# lite_version.net
KiCad netlist of a schematic drawn in EAGLE
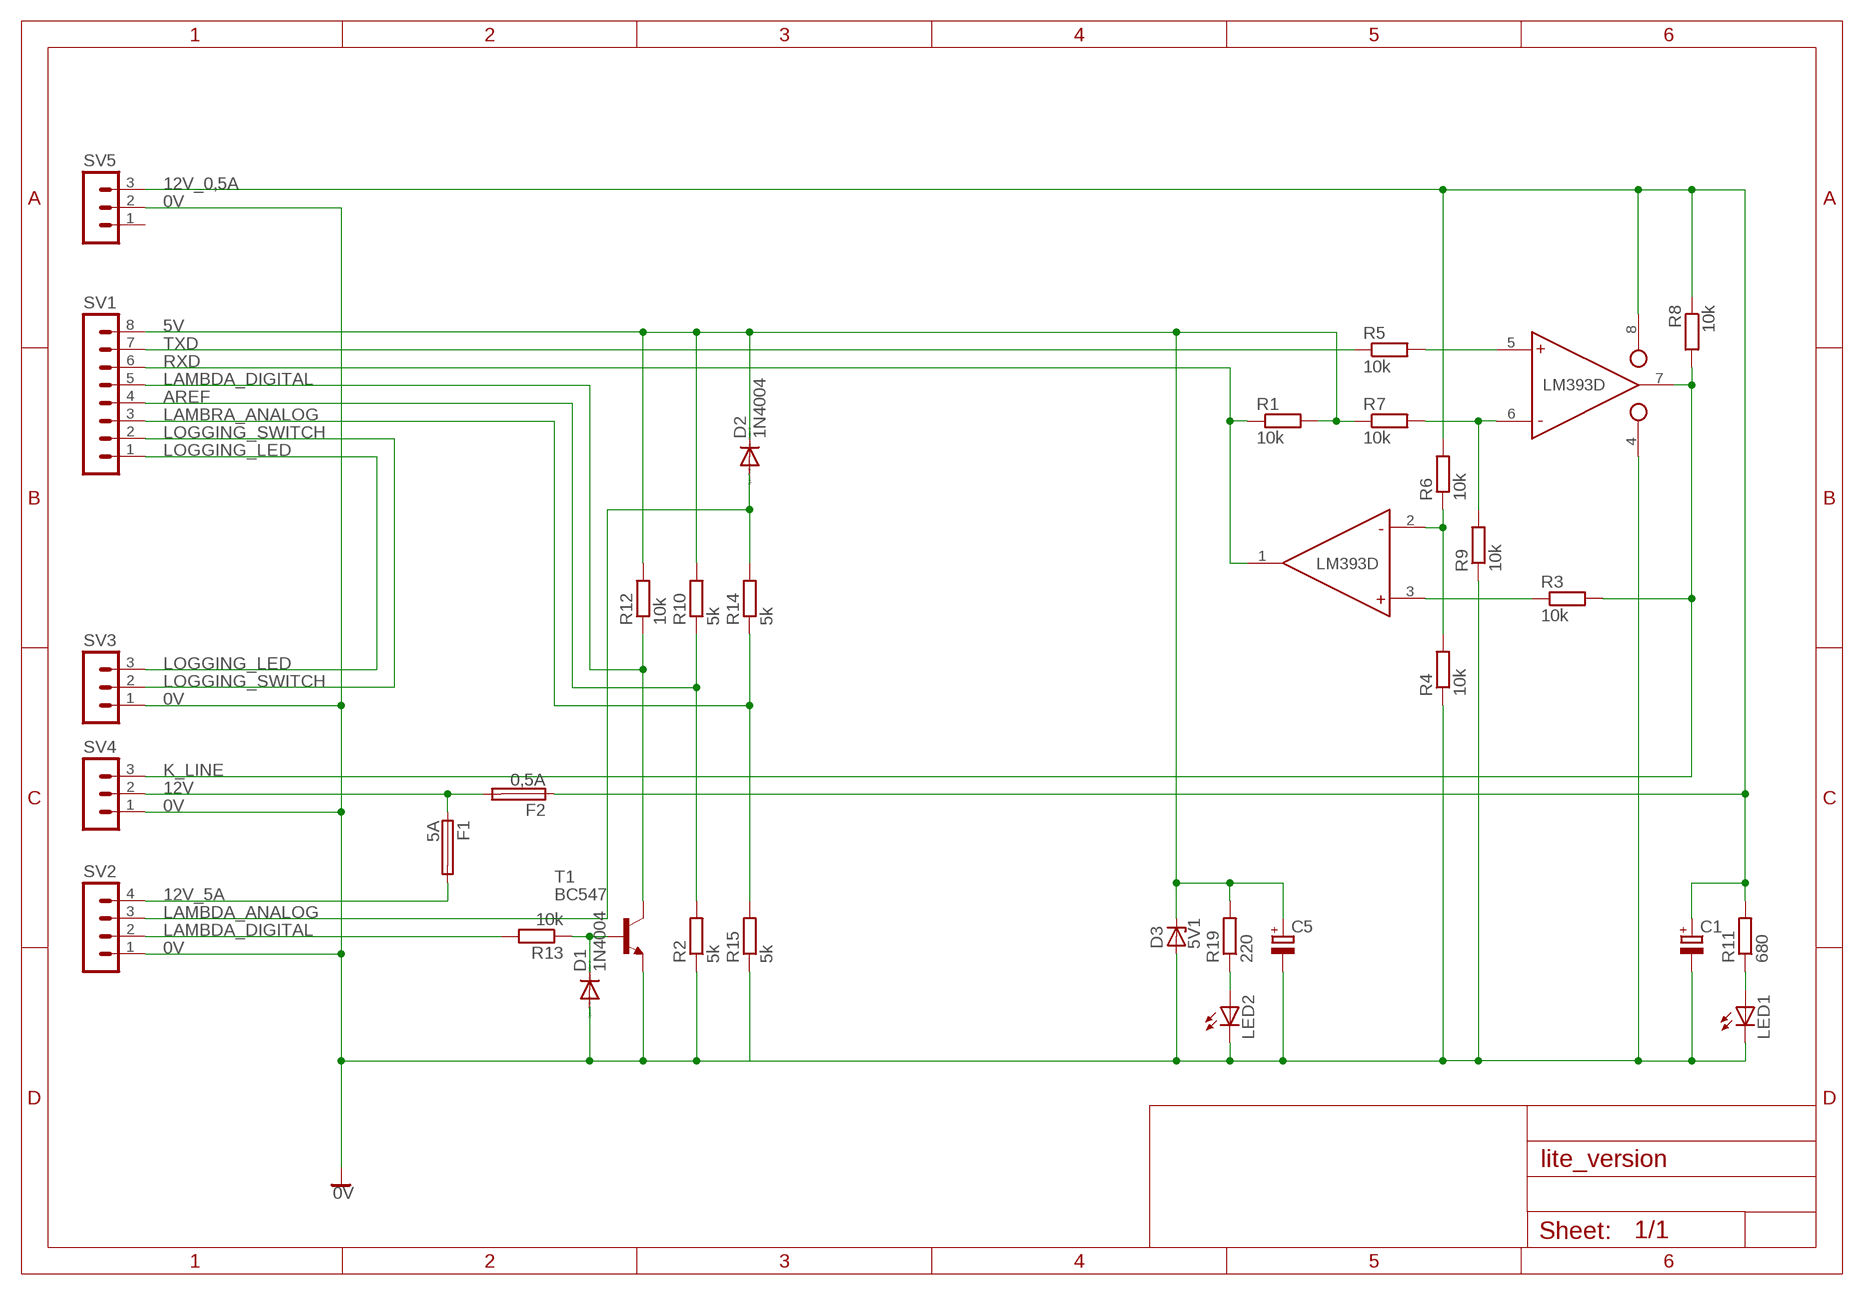
[diagram p0: schematic, sheet 1]

(export (version "E")
  (design (tool "Eeschema 10.0.6"))
  (components
    (comp (ref "C1")
      (value "CPOL-EUE1.8-4")
      (footprint "eagle-import:E1,8-4")
      (libsource (lib "eagle-import") (part "CPOL-EUE1.8-4"))
    )
    (comp (ref "C5")
      (value "CPOL-EUE1.8-4")
      (footprint "eagle-import:E1,8-4")
      (libsource (lib "eagle-import") (part "CPOL-EUE1.8-4"))
    )
    (comp (ref "D1")
      (value "1N4004")
      (footprint "eagle-import:DO41-10")
      (libsource (lib "eagle-import") (part "1N4004"))
    )
    (comp (ref "D2")
      (value "1N4004")
      (footprint "eagle-import:DO41-10")
      (libsource (lib "eagle-import") (part "1N4004"))
    )
    (comp (ref "D3")
      (value "5V1")
      (footprint "eagle-import:DO34Z7")
      (libsource (lib "eagle-import") (part "ZENER-DIODEDO34-7"))
    )
    (comp (ref "F1")
      (value "5A")
      (footprint "eagle-import:SH22,5")
      (fields (field (name "MF") "SCHURTER") (field (name "MPN") "0031.8201"))
      (libsource (lib "eagle-import") (part "SH22,5"))
    )
    (comp (ref "F2")
      (value "0,5A")
      (footprint "eagle-import:SH22,5")
      (fields (field (name "MF") "SCHURTER") (field (name "MPN") "0031.8201"))
      (libsource (lib "eagle-import") (part "SH22,5"))
    )
    (comp (ref "LED1")
      (value "LED5MM")
      (footprint "eagle-import:LED5MM")
      (libsource (lib "eagle-import") (part "LED5MM"))
    )
    (comp (ref "LED2")
      (value "LED5MM")
      (footprint "eagle-import:LED5MM")
      (libsource (lib "eagle-import") (part "LED5MM"))
    )
    (comp (ref "R1")
      (value "10k")
      (footprint "eagle-import:0207_7")
      (libsource (lib "eagle-import") (part "R-EU_0207/7"))
    )
    (comp (ref "R2")
      (value "5k")
      (footprint "eagle-import:0207_7")
      (libsource (lib "eagle-import") (part "R-EU_0207/7"))
    )
    (comp (ref "R3")
      (value "10k")
      (footprint "eagle-import:0207_7")
      (libsource (lib "eagle-import") (part "R-EU_0207/7"))
    )
    (comp (ref "R4")
      (value "10k")
      (footprint "eagle-import:0207_7")
      (libsource (lib "eagle-import") (part "R-EU_0207/7"))
    )
    (comp (ref "R5")
      (value "10k")
      (footprint "eagle-import:0207_7")
      (libsource (lib "eagle-import") (part "R-EU_0207/7"))
    )
    (comp (ref "R6")
      (value "10k")
      (footprint "eagle-import:0207_7")
      (libsource (lib "eagle-import") (part "R-EU_0207/7"))
    )
    (comp (ref "R7")
      (value "10k")
      (footprint "eagle-import:0207_7")
      (libsource (lib "eagle-import") (part "R-EU_0207/7"))
    )
    (comp (ref "R8")
      (value "10k")
      (footprint "eagle-import:0207_7")
      (libsource (lib "eagle-import") (part "R-EU_0207/7"))
    )
    (comp (ref "R9")
      (value "10k")
      (footprint "eagle-import:0207_7")
      (libsource (lib "eagle-import") (part "R-EU_0207/7"))
    )
    (comp (ref "R10")
      (value "5k")
      (footprint "eagle-import:0207_7")
      (libsource (lib "eagle-import") (part "R-EU_0207/7"))
    )
    (comp (ref "R11")
      (value "680")
      (footprint "eagle-import:0207_7")
      (libsource (lib "eagle-import") (part "R-EU_0207/7"))
    )
    (comp (ref "R12")
      (value "10k")
      (footprint "eagle-import:0207_7")
      (libsource (lib "eagle-import") (part "R-EU_0207/7"))
    )
    (comp (ref "R13")
      (value "10k")
      (footprint "eagle-import:0207_7")
      (libsource (lib "eagle-import") (part "R-EU_0207/7"))
    )
    (comp (ref "R14")
      (value "5k")
      (footprint "eagle-import:0207_7")
      (libsource (lib "eagle-import") (part "R-EU_0207/7"))
    )
    (comp (ref "R15")
      (value "5k")
      (footprint "eagle-import:0207_7")
      (libsource (lib "eagle-import") (part "R-EU_0207/7"))
    )
    (comp (ref "R19")
      (value "220")
      (footprint "eagle-import:0207_7")
      (libsource (lib "eagle-import") (part "R-EU_0207/7"))
    )
    (comp (ref "SV1")
      (value "MA08-1")
      (footprint "eagle-import:MA08-1")
      (libsource (lib "eagle-import") (part "MA08-1"))
    )
    (comp (ref "SV2")
      (value "MA04-1")
      (footprint "eagle-import:MA04-1")
      (libsource (lib "eagle-import") (part "MA04-1"))
    )
    (comp (ref "SV3")
      (value "MA03-1")
      (footprint "eagle-import:MA03-1")
      (libsource (lib "eagle-import") (part "MA03-1"))
    )
    (comp (ref "SV4")
      (value "MA03-1")
      (footprint "eagle-import:MA03-1")
      (libsource (lib "eagle-import") (part "MA03-1"))
    )
    (comp (ref "SV5")
      (value "MA03-1")
      (footprint "eagle-import:MA03-1")
      (libsource (lib "eagle-import") (part "MA03-1"))
    )
    (comp (ref "T1")
      (value "BC547")
      (footprint "eagle-import:TO92")
      (libsource (lib "eagle-import") (part "BC547"))
    )
    (comp (ref "U$1")
      (value "LM393D")
      (footprint "eagle-import:LM393D")
      (libsource (lib "eagle-import") (part "LM393D"))
    )
  )
  (nets
    (net (code "1") (name "/5V") (class "Default")
      (node (ref "C5") (pin "+") (pinfunction "+_+") (pintype "passive"))
      (node (ref "D2") (pin "C") (pinfunction "C_C") (pintype "passive"))
      (node (ref "D3") (pin "C") (pinfunction "C_C") (pintype "passive"))
      (node (ref "R1") (pin "2") (pinfunction "2_2") (pintype "passive"))
      (node (ref "R10") (pin "2") (pinfunction "2_2") (pintype "passive"))
      (node (ref "R12") (pin "2") (pinfunction "2_2") (pintype "passive"))
      (node (ref "R19") (pin "2") (pinfunction "2_2") (pintype "passive"))
      (node (ref "R7") (pin "1") (pinfunction "1_1") (pintype "passive"))
      (node (ref "SV1") (pin "8") (pinfunction "8_8") (pintype "passive"))
    )
    (net (code "2") (name "/12V") (class "Default")
      (node (ref "F1") (pin "1") (pinfunction "1_1") (pintype "passive"))
      (node (ref "F2") (pin "2") (pinfunction "2_2") (pintype "passive"))
      (node (ref "SV4") (pin "2") (pinfunction "2_2") (pintype "passive"))
    )
    (net (code "3") (name "/12V_0,5A") (class "Default")
      (node (ref "C1") (pin "+") (pinfunction "+_+") (pintype "passive"))
      (node (ref "F2") (pin "1") (pinfunction "1_1") (pintype "passive"))
      (node (ref "R11") (pin "2") (pinfunction "2_2") (pintype "passive"))
      (node (ref "R6") (pin "2") (pinfunction "2_2") (pintype "passive"))
      (node (ref "R8") (pin "1") (pinfunction "1_1") (pintype "passive"))
      (node (ref "SV5") (pin "3") (pinfunction "3_3") (pintype "passive"))
      (node (ref "U$1") (pin "8") (pinfunction "VCC_8") (pintype "power_in"))
    )
    (net (code "4") (name "/12V_5A") (class "Default")
      (node (ref "F1") (pin "2") (pinfunction "2_2") (pintype "passive"))
      (node (ref "SV2") (pin "4") (pinfunction "4_4") (pintype "passive"))
    )
    (net (code "5") (name "/AREF") (class "Default")
      (node (ref "R10") (pin "1") (pinfunction "1_1") (pintype "passive"))
      (node (ref "R2") (pin "2") (pinfunction "2_2") (pintype "passive"))
      (node (ref "SV1") (pin "4") (pinfunction "4_4") (pintype "passive"))
    )
    (net (code "6") (name "/K_LINE") (class "Default")
      (node (ref "R3") (pin "2") (pinfunction "2_2") (pintype "passive"))
      (node (ref "R8") (pin "2") (pinfunction "2_2") (pintype "passive"))
      (node (ref "SV4") (pin "3") (pinfunction "3_3") (pintype "passive"))
      (node (ref "U$1") (pin "7") (pinfunction "OUT_7") (pintype "output"))
    )
    (net (code "7") (name "/LAMBDA_ANALOG") (class "Default")
      (node (ref "D2") (pin "A") (pinfunction "A_A") (pintype "passive"))
      (node (ref "R14") (pin "2") (pinfunction "2_2") (pintype "passive"))
      (node (ref "SV2") (pin "3") (pinfunction "3_3") (pintype "passive"))
    )
    (net (code "8") (name "/LAMBDA_DIGITAL") (class "Default")
      (node (ref "R12") (pin "1") (pinfunction "1_1") (pintype "passive"))
      (node (ref "R13") (pin "2") (pinfunction "2_2") (pintype "passive"))
      (node (ref "SV1") (pin "5") (pinfunction "5_5") (pintype "passive"))
      (node (ref "SV2") (pin "2") (pinfunction "2_2") (pintype "passive"))
      (node (ref "T1") (pin "3") (pinfunction "C_3") (pintype "passive"))
    )
    (net (code "9") (name "/LAMBRA_ANALOG") (class "Default")
      (node (ref "R14") (pin "1") (pinfunction "1_1") (pintype "passive"))
      (node (ref "R15") (pin "2") (pinfunction "2_2") (pintype "passive"))
      (node (ref "SV1") (pin "3") (pinfunction "3_3") (pintype "passive"))
    )
    (net (code "10") (name "/LOGGING_LED") (class "Default")
      (node (ref "SV1") (pin "1") (pinfunction "1_1") (pintype "passive"))
      (node (ref "SV3") (pin "3") (pinfunction "3_3") (pintype "passive"))
    )
    (net (code "11") (name "/LOGGING_SWITCH") (class "Default")
      (node (ref "SV1") (pin "2") (pinfunction "2_2") (pintype "passive"))
      (node (ref "SV3") (pin "2") (pinfunction "2_2") (pintype "passive"))
    )
    (net (code "12") (name "/RXD") (class "Default")
      (node (ref "R1") (pin "1") (pinfunction "1_1") (pintype "passive"))
      (node (ref "SV1") (pin "6") (pinfunction "6_6") (pintype "passive"))
      (node (ref "U$1") (pin "1") (pinfunction "OUT_1") (pintype "output"))
    )
    (net (code "13") (name "/TXD") (class "Default")
      (node (ref "R5") (pin "1") (pinfunction "1_1") (pintype "passive"))
      (node (ref "SV1") (pin "7") (pinfunction "7_7") (pintype "passive"))
    )
    (net (code "14") (name "0V") (class "Default")
      (node (ref "C1") (pin "-") (pinfunction "-_-") (pintype "passive"))
      (node (ref "C5") (pin "-") (pinfunction "-_-") (pintype "passive"))
      (node (ref "D1") (pin "A") (pinfunction "A_A") (pintype "passive"))
      (node (ref "D3") (pin "A") (pinfunction "A_A") (pintype "passive"))
      (node (ref "LED1") (pin "K") (pinfunction "C_K") (pintype "passive"))
      (node (ref "LED2") (pin "K") (pinfunction "C_K") (pintype "passive"))
      (node (ref "R15") (pin "1") (pinfunction "1_1") (pintype "passive"))
      (node (ref "R2") (pin "1") (pinfunction "1_1") (pintype "passive"))
      (node (ref "R4") (pin "1") (pinfunction "1_1") (pintype "passive"))
      (node (ref "R9") (pin "1") (pinfunction "1_1") (pintype "passive"))
      (node (ref "SV2") (pin "1") (pinfunction "1_1") (pintype "passive"))
      (node (ref "SV3") (pin "1") (pinfunction "1_1") (pintype "passive"))
      (node (ref "SV4") (pin "1") (pinfunction "1_1") (pintype "passive"))
      (node (ref "SV5") (pin "2") (pinfunction "2_2") (pintype "passive"))
      (node (ref "T1") (pin "1") (pinfunction "E_1") (pintype "passive"))
      (node (ref "U$1") (pin "4") (pinfunction "GND_4") (pintype "power_in"))
    )
    (net (code "15") (name "Net-(LED1-PadA)") (class "Default")
      (node (ref "LED1") (pin "A") (pinfunction "A_A") (pintype "passive"))
      (node (ref "R11") (pin "1") (pinfunction "1_1") (pintype "passive"))
    )
    (net (code "16") (name "Net-(LED2-PadA)") (class "Default")
      (node (ref "LED2") (pin "A") (pinfunction "A_A") (pintype "passive"))
      (node (ref "R19") (pin "1") (pinfunction "1_1") (pintype "passive"))
    )
    (net (code "17") (name "Net-(T1-B)") (class "Default")
      (node (ref "D1") (pin "C") (pinfunction "C_C") (pintype "passive"))
      (node (ref "R13") (pin "1") (pinfunction "1_1") (pintype "passive"))
      (node (ref "T1") (pin "2") (pinfunction "B_2") (pintype "passive"))
    )
    (net (code "18") (name "Net-(U$1B-IN+)") (class "Default")
      (node (ref "R3") (pin "1") (pinfunction "1_1") (pintype "passive"))
      (node (ref "U$1") (pin "3") (pinfunction "IN+_3") (pintype "input"))
    )
    (net (code "19") (name "Net-(U$1B-IN-)") (class "Default")
      (node (ref "R4") (pin "2") (pinfunction "2_2") (pintype "passive"))
      (node (ref "R6") (pin "1") (pinfunction "1_1") (pintype "passive"))
      (node (ref "U$1") (pin "2") (pinfunction "IN-_2") (pintype "input"))
    )
    (net (code "20") (name "Net-(U$1C-IN+)") (class "Default")
      (node (ref "R5") (pin "2") (pinfunction "2_2") (pintype "passive"))
      (node (ref "U$1") (pin "5") (pinfunction "IN+_5") (pintype "input"))
    )
    (net (code "21") (name "Net-(U$1C-IN-)") (class "Default")
      (node (ref "R7") (pin "2") (pinfunction "2_2") (pintype "passive"))
      (node (ref "R9") (pin "2") (pinfunction "2_2") (pintype "passive"))
      (node (ref "U$1") (pin "6") (pinfunction "IN-_6") (pintype "input"))
    )
    (net (code "22") (name "unconnected-(SV5-Pad1)") (class "Default")
      (node (ref "SV5") (pin "1") (pinfunction "1_1") (pintype "passive"))
    )
  )
)
